# MCU099_04_XDS110_Target_Interface.net
KiCad netlist of a schematic drawn in Altium Designer
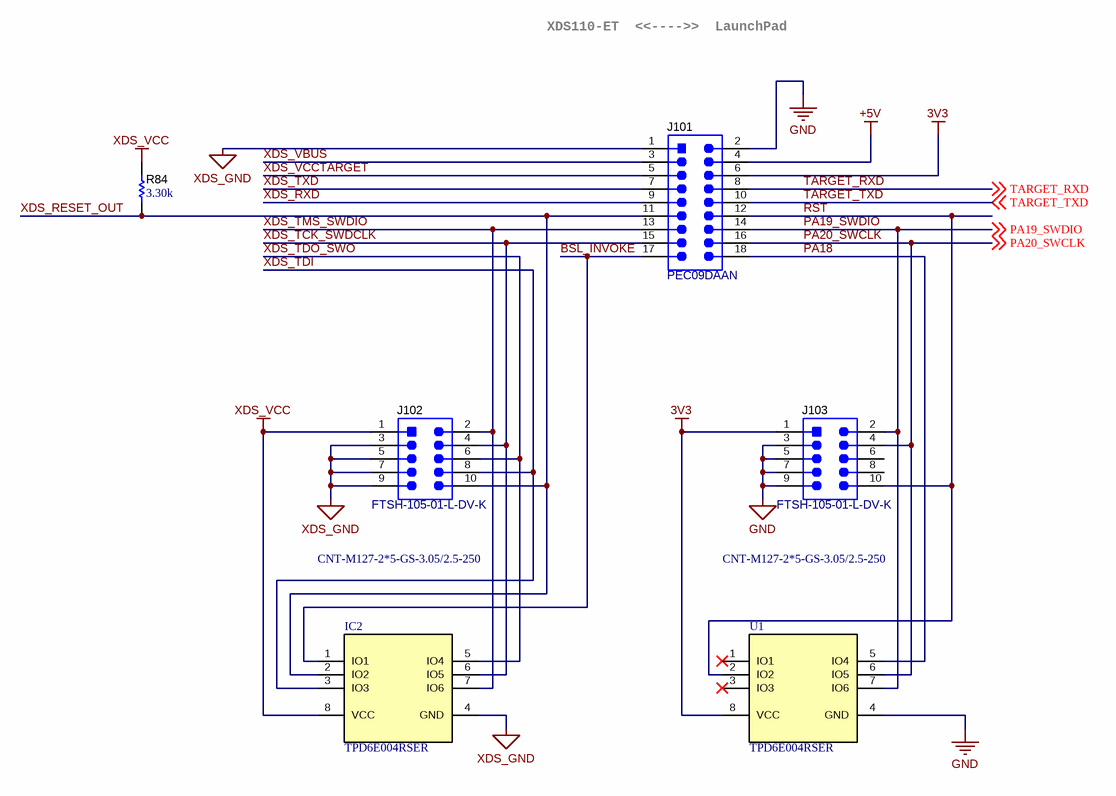
[diagram p0: MCU099_04_XDS110_Target_Interface.SchDoc]

(export (version "E")
  (design (tool "Eeschema 10.0.6"))
  (components
    (comp (ref "IC2")
      (value "TPD6E004RSER")
      (footprint "RSE0008A")
      (fields (field (name "MANUFACTURER") "Texas Instruments") (field (name "PARTNUMBER") "TPD6E004RSER"))
      (libsource (lib "Altium Vault - TI") (part "TI-TPD6E004-UQFN_RSE-8"))
    )
    (comp (ref "J101")
      (value "PEC09DAAN")
      (footprint "Sullins_PxC09DAAN")
      (description "Header, 2.54mm, 9x2, Tin, TH")
      (fields
        (field (name "MANUFACTURER") "Sullins Connector Solutions")
        (field (name "PUBLISHER") "Texas Instruments")
      )
      (libsource (lib "Altium Vault - TI") (part "Header_9x2"))
    )
    (comp (ref "J102")
      (value "FTSH-105-01-L-DV-K")
      (footprint "Samtec_FTSH-105-01-x-DV-K")
      (description "Header(Shrouded), 1.27mm, 5x2, Gold, SMT")
      (fields (field (name "MANUFACTURER") "Samtec") (field (name "PUBLISHER") "Texas Instruments"))
      (libsource (lib "Altium Vault - TI") (part "Header_5x2"))
    )
    (comp (ref "J103")
      (value "FTSH-105-01-L-DV-K")
      (footprint "Samtec_FTSH-105-01-x-DV-K")
      (description "Header(Shrouded), 1.27mm, 5x2, Gold, SMT")
      (fields (field (name "MANUFACTURER") "Samtec") (field (name "PUBLISHER") "Texas Instruments"))
      (libsource (lib "Altium Vault - TI") (part "Header_5x2"))
    )
    (comp (ref "R84")
      (value "ERJ-2RKF3301X")
      (footprint "0402")
      (description "RES, 3.30 k, 1%, 0.1 W, AEC-Q200 Grade 0, 0402")
      (fields
        (field (name "MANUFACTURER") "Panasonic")
        (field (name "VALUEDISPLAYED") "3.30k")
        (field (name "PUBLISHER") "Texas Instruments")
      )
      (libsource (lib "Altium Vault - TI") (part "Resistor"))
    )
    (comp (ref "U1")
      (value "TPD6E004RSER")
      (footprint "RSE0008A")
      (fields (field (name "MANUFACTURER") "Texas Instruments") (field (name "PARTNUMBER") "TPD6E004RSER"))
      (libsource (lib "Altium Vault - TI") (part "TI-TPD6E004-UQFN_RSE-8"))
    )
  )
  (nets
    (net (code "1") (name "+5V") (class "Default")
      (node (ref "J101") (pin "4") (pinfunction "4_4") (pintype "passive"))
    )
    (net (code "2") (name "/BSL_INVOKE") (class "Default")
      (node (ref "IC2") (pin "1") (pinfunction "IO1_1") (pintype "passive"))
      (node (ref "J101") (pin "17") (pinfunction "17_17") (pintype "passive"))
    )
    (net (code "3") (name "/PA18") (class "Default")
      (node (ref "J101") (pin "18") (pinfunction "18_18") (pintype "passive"))
      (node (ref "U1") (pin "5") (pinfunction "IO4_5") (pintype "passive"))
    )
    (net (code "4") (name "/XDS_RESET_OUT") (class "Default")
      (node (ref "IC2") (pin "2") (pinfunction "IO2_2") (pintype "passive"))
      (node (ref "J101") (pin "11") (pinfunction "11_11") (pintype "passive"))
      (node (ref "J102") (pin "10") (pinfunction "10_10") (pintype "passive"))
      (node (ref "R84") (pin "1") (pinfunction "1_1") (pintype "passive"))
    )
    (net (code "5") (name "/XDS_RXD") (class "Default")
      (node (ref "J101") (pin "9") (pinfunction "9_9") (pintype "passive"))
    )
    (net (code "6") (name "/XDS_TCK_SWDCLK") (class "Default")
      (node (ref "IC2") (pin "6") (pinfunction "IO5_6") (pintype "passive"))
      (node (ref "J101") (pin "15") (pinfunction "15_15") (pintype "passive"))
      (node (ref "J102") (pin "4") (pinfunction "4_4") (pintype "passive"))
    )
    (net (code "7") (name "/XDS_TDI") (class "Default")
      (node (ref "IC2") (pin "3") (pinfunction "IO3_3") (pintype "passive"))
      (node (ref "J102") (pin "8") (pinfunction "8_8") (pintype "passive"))
    )
    (net (code "8") (name "/XDS_TDO_SWO") (class "Default")
      (node (ref "IC2") (pin "5") (pinfunction "IO4_5") (pintype "passive"))
      (node (ref "J102") (pin "6") (pinfunction "6_6") (pintype "passive"))
    )
    (net (code "9") (name "/XDS_TMS_SWDIO") (class "Default")
      (node (ref "IC2") (pin "7") (pinfunction "IO6_7") (pintype "passive"))
      (node (ref "J101") (pin "13") (pinfunction "13_13") (pintype "passive"))
      (node (ref "J102") (pin "2") (pinfunction "2_2") (pintype "passive"))
    )
    (net (code "10") (name "/XDS_TXD") (class "Default")
      (node (ref "J101") (pin "7") (pinfunction "7_7") (pintype "passive"))
    )
    (net (code "11") (name "/XDS_VBUS") (class "Default")
      (node (ref "J101") (pin "3") (pinfunction "3_3") (pintype "passive"))
    )
    (net (code "12") (name "/XDS_VCCTARGET") (class "Default")
      (node (ref "J101") (pin "5") (pinfunction "5_5") (pintype "passive"))
    )
    (net (code "13") (name "/~{RST}") (class "Default")
      (node (ref "J101") (pin "12") (pinfunction "12_12") (pintype "passive"))
      (node (ref "J103") (pin "10") (pinfunction "10_10") (pintype "passive"))
      (node (ref "U1") (pin "2") (pinfunction "IO2_2") (pintype "passive"))
    )
    (net (code "14") (name "3V3") (class "Default")
      (node (ref "J101") (pin "6") (pinfunction "6_6") (pintype "passive"))
      (node (ref "J103") (pin "1") (pinfunction "1_1") (pintype "passive"))
      (node (ref "U1") (pin "8") (pinfunction "VCC_8") (pintype "power_in"))
    )
    (net (code "15") (name "GND") (class "Default")
      (node (ref "J101") (pin "2") (pinfunction "2_2") (pintype "passive"))
      (node (ref "J103") (pin "3") (pinfunction "3_3") (pintype "passive"))
      (node (ref "J103") (pin "5") (pinfunction "5_5") (pintype "passive"))
      (node (ref "J103") (pin "7") (pinfunction "7_7") (pintype "passive"))
      (node (ref "J103") (pin "9") (pinfunction "9_9") (pintype "passive"))
      (node (ref "U1") (pin "4") (pinfunction "GND_4") (pintype "power_in"))
    )
    (net (code "16") (name "PA19_SWDIO") (class "Default")
      (node (ref "J101") (pin "14") (pinfunction "14_14") (pintype "passive"))
      (node (ref "J103") (pin "2") (pinfunction "2_2") (pintype "passive"))
      (node (ref "U1") (pin "7") (pinfunction "IO6_7") (pintype "passive"))
    )
    (net (code "17") (name "PA20_SWCLK") (class "Default")
      (node (ref "J101") (pin "16") (pinfunction "16_16") (pintype "passive"))
      (node (ref "J103") (pin "4") (pinfunction "4_4") (pintype "passive"))
      (node (ref "U1") (pin "6") (pinfunction "IO5_6") (pintype "passive"))
    )
    (net (code "18") (name "TARGET_RXD") (class "Default")
      (node (ref "J101") (pin "8") (pinfunction "8_8") (pintype "passive"))
    )
    (net (code "19") (name "TARGET_TXD") (class "Default")
      (node (ref "J101") (pin "10") (pinfunction "10_10") (pintype "passive"))
    )
    (net (code "20") (name "XDS_GND") (class "Default")
      (node (ref "IC2") (pin "4") (pinfunction "GND_4") (pintype "power_in"))
      (node (ref "J101") (pin "1") (pinfunction "1_1") (pintype "passive"))
      (node (ref "J102") (pin "3") (pinfunction "3_3") (pintype "passive"))
      (node (ref "J102") (pin "5") (pinfunction "5_5") (pintype "passive"))
      (node (ref "J102") (pin "7") (pinfunction "7_7") (pintype "passive"))
      (node (ref "J102") (pin "9") (pinfunction "9_9") (pintype "passive"))
    )
    (net (code "21") (name "XDS_VCC") (class "Default")
      (node (ref "IC2") (pin "8") (pinfunction "VCC_8") (pintype "power_in"))
      (node (ref "J102") (pin "1") (pinfunction "1_1") (pintype "passive"))
      (node (ref "R84") (pin "2") (pinfunction "2_2") (pintype "passive"))
    )
    (net (code "22") (name "unconnected-(J103-Pad6)") (class "Default")
      (node (ref "J103") (pin "6") (pinfunction "6_6") (pintype "passive"))
    )
    (net (code "23") (name "unconnected-(J103-Pad8)") (class "Default")
      (node (ref "J103") (pin "8") (pinfunction "8_8") (pintype "passive"))
    )
    (net (code "24") (name "unconnected-(U1-IO1-Pad1)") (class "Default")
      (node (ref "U1") (pin "1") (pinfunction "IO1_1") (pintype "passive+no_connect"))
    )
    (net (code "25") (name "unconnected-(U1-IO3-Pad3)") (class "Default")
      (node (ref "U1") (pin "3") (pinfunction "IO3_3") (pintype "passive+no_connect"))
    )
  )
)
